# AmbaSat-08-GPS_TESEO.net
KiCad netlist of a schematic drawn in EAGLE
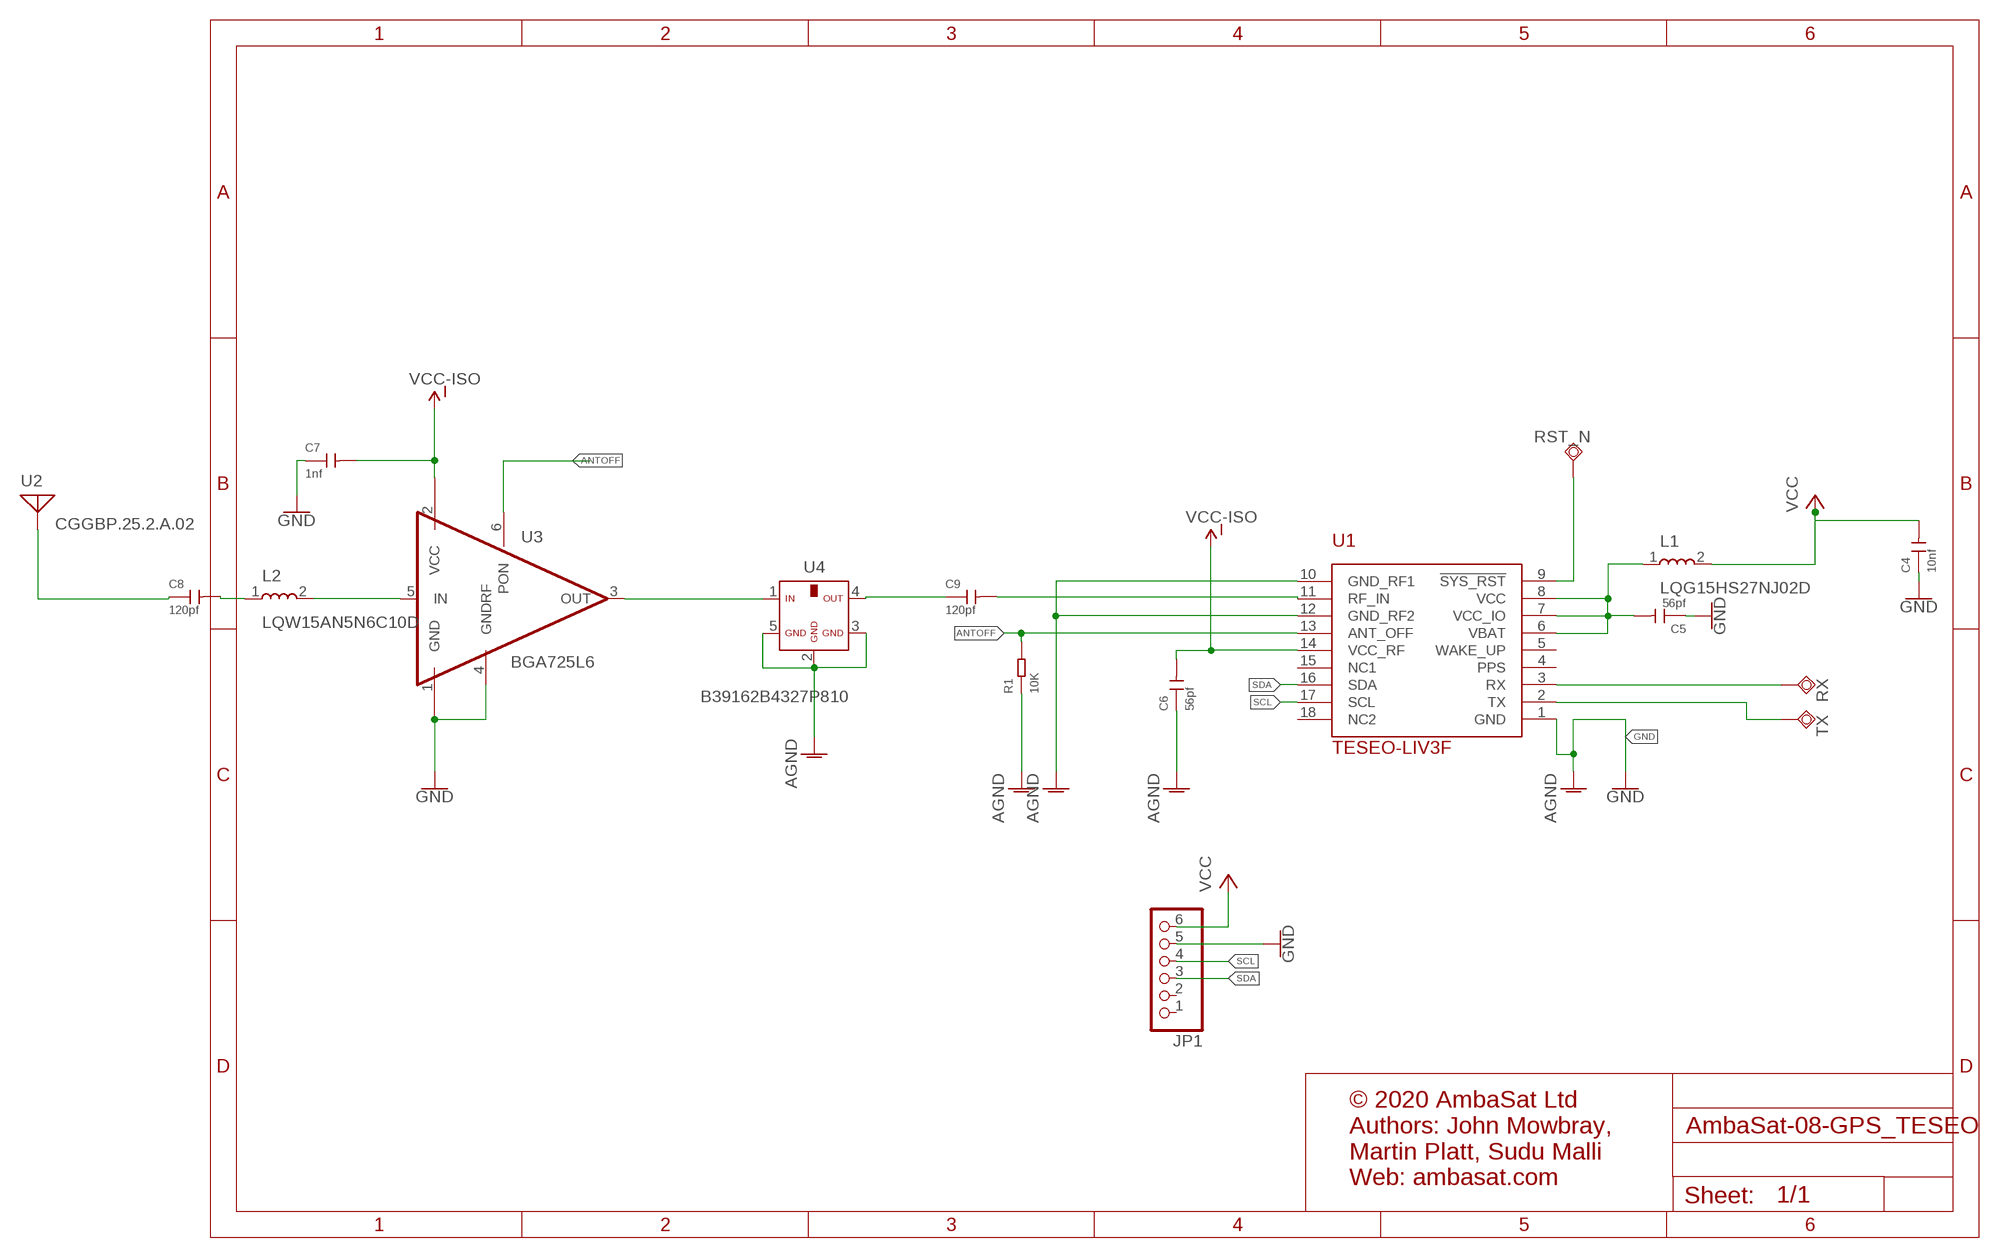
[diagram p0: schematic, sheet 1]

(export (version "E")
  (design (tool "Eeschema 10.0.6"))
  (components
    (comp (ref "C4")
      (value "10nf")
      (footprint "eagle-import:C0805")
      (fields (field (name "MPN") "CC0805JRX7R9BB103"))
      (libsource (lib "eagle-import") (part "CERAMIC-10NF-50V-5%-X7R(0805)"))
    )
    (comp (ref "C5")
      (value "56pf")
      (footprint "eagle-import:C0805")
      (fields (field (name "MPN") "CC0805JRX7R9BB103") (field (name "MPN_1") "CC0805FRNPO9BN560"))
      (libsource (lib "eagle-import") (part "CERAMIC-10NF-50V-5%-X7R(0805)"))
    )
    (comp (ref "C6")
      (value "56pf")
      (footprint "eagle-import:C0805")
      (fields (field (name "MPN") "CC0805JRX7R9BB103") (field (name "MPN_1") "CC0805FRNPO9BN560"))
      (libsource (lib "eagle-import") (part "CERAMIC-10NF-50V-5%-X7R(0805)"))
    )
    (comp (ref "C7")
      (value "1nf")
      (footprint "eagle-import:C0805")
      (fields (field (name "MPN") "CC0805JRX7R9BB103") (field (name "MPN_1") "CC0805JRX7R9BB102"))
      (libsource (lib "eagle-import") (part "CERAMIC-10NF-50V-5%-X7R(0805)"))
    )
    (comp (ref "C8")
      (value "120pf")
      (footprint "eagle-import:C0402")
      (fields (field (name "MPN") "CC0402JRNPO9BN101") (field (name "MPN_1") "CC0402JRNPO9BN121"))
      (libsource (lib "eagle-import") (part "CERAMIC-100PF-50V-5%-NPO(0402)"))
    )
    (comp (ref "C9")
      (value "120pf")
      (footprint "eagle-import:C0402")
      (fields (field (name "MPN") "CC0402JRNPO9BN101") (field (name "MPN_1") "CC0402JRNPO9BN121"))
      (libsource (lib "eagle-import") (part "CERAMIC-100PF-50V-5%-NPO(0402)"))
    )
    (comp (ref "JP1")
      (value "HEADER-1X6")
      (footprint "eagle-import:1X06_OVAL")
      (libsource (lib "eagle-import") (part "HEADER-1X6"))
    )
    (comp (ref "L1")
      (value "LQG15HS27NJ02D")
      (footprint "eagle-import:LQG15HN2N2S02D")
      (fields
        (field (name "DIGIKEY_PART_NUMBER") "490-1077-2-ND")
        (field (name "MANUFACTURER") "Murata Electronics North America")
        (field (name "MPN") "LQG15HN2N2S02D")
        (field (name "DIGIKEY_PART_NUMBER_1") "490-2628-1-ND")
        (field (name "MPN_1") "LQG15HS27NJ02D")
        (field (name "CREATED_BY") "PCBLayout.com")
      )
      (libsource (lib "eagle-import") (part "LQG15HN2N2S02D"))
    )
    (comp (ref "L2")
      (value "LQW15AN5N6C10D")
      (footprint "eagle-import:LQG15HN2N2S02D")
      (fields
        (field (name "DIGIKEY_PART_NUMBER") "490-1077-2-ND")
        (field (name "MANUFACTURER") "Murata Electronics North America")
        (field (name "MPN") "LQG15HN2N2S02D")
        (field (name "DIGIKEY_PART_NUMBER_1") "490-6833-1-ND")
        (field (name "MPN_1") "LQW15AN5N6C10D")
        (field (name "CREATED_BY") "PCBLayout.com")
      )
      (libsource (lib "eagle-import") (part "LQG15HN2N2S02D"))
    )
    (comp (ref "R1")
      (value "10K")
      (footprint "eagle-import:R0805")
      (fields (field (name "MPN") "RC0805FR-0710KL"))
      (libsource (lib "eagle-import") (part "SMD-RES-10K-1%-1/8W(0805)"))
    )
    (comp (ref "RST_N")
      (value "TESTPAD_TPSQTP11SQ")
      (footprint "eagle-import:TESTPAD_TP11SQ")
      (libsource (lib "eagle-import") (part "TESTPAD_TPSQTP11SQ"))
    )
    (comp (ref "RX")
      (value "TESTPAD_TPSQTP11SQ")
      (footprint "eagle-import:TESTPAD_TP11SQ")
      (libsource (lib "eagle-import") (part "TESTPAD_TPSQTP11SQ"))
    )
    (comp (ref "TX")
      (value "TESTPAD_TPSQTP11SQ")
      (footprint "eagle-import:TESTPAD_TP11SQ")
      (libsource (lib "eagle-import") (part "TESTPAD_TPSQTP11SQ"))
    )
    (comp (ref "U1")
      (value "TESEO-LIV3F")
      (footprint "eagle-import:TESEO-LIV3F")
      (libsource (lib "eagle-import") (part "TESEO-LIV3F"))
    )
    (comp (ref "U2")
      (value "CGGBP.25.2.A.02")
      (footprint "eagle-import:ANTENNA-PATCH")
      (libsource (lib "eagle-import") (part "CGGBP.25.2.A.02"))
    )
    (comp (ref "U3")
      (value "BGA725L6")
      (footprint "eagle-import:PSON35P100X100X35-6N")
      (fields (field (name "MPN") "BGA725L6E6327FTSA1"))
      (libsource (lib "eagle-import") (part "BGA725L6"))
    )
    (comp (ref "U4")
      (value "B39162B4327P810")
      (footprint "eagle-import:FIL_B39162B9417K610")
      (libsource (lib "eagle-import") (part "B39162B4327P810"))
    )
  )
  (nets
    (net (code "1") (name "ANTOFF") (class "Default")
      (node (ref "R1") (pin "2") (pinfunction "2_2") (pintype "passive"))
      (node (ref "U1") (pin "13") (pinfunction "ANT_OFF_13") (pintype "output"))
      (node (ref "U3") (pin "6") (pinfunction "PON_6") (pintype "power_in"))
    )
    (net (code "2") (name "GND") (class "Default")
      (node (ref "C4") (pin "1") (pinfunction "1_1") (pintype "passive"))
      (node (ref "C5") (pin "1") (pinfunction "1_1") (pintype "passive"))
      (node (ref "C6") (pin "1") (pinfunction "1_1") (pintype "passive"))
      (node (ref "C7") (pin "1") (pinfunction "1_1") (pintype "passive"))
      (node (ref "JP1") (pin "5") (pinfunction "5_5") (pintype "passive"))
      (node (ref "R1") (pin "1") (pinfunction "1_1") (pintype "passive"))
      (node (ref "U1") (pin "1") (pinfunction "GND_1") (pintype "power_in"))
      (node (ref "U1") (pin "10") (pinfunction "GND_RF1_10") (pintype "power_in"))
      (node (ref "U1") (pin "12") (pinfunction "GND_RF2_12") (pintype "power_in"))
      (node (ref "U3") (pin "1") (pinfunction "GND_1") (pintype "bidirectional"))
      (node (ref "U3") (pin "4") (pinfunction "GNDRF_4") (pintype "bidirectional"))
      (node (ref "U4") (pin "2") (pinfunction "GND3_2") (pintype "passive"))
      (node (ref "U4") (pin "3") (pinfunction "GND2_3") (pintype "passive"))
      (node (ref "U4") (pin "5") (pinfunction "GND_5") (pintype "passive"))
    )
    (net (code "3") (name "Net-(C8-Pad2)") (class "Default")
      (node (ref "C8") (pin "2") (pinfunction "2_2") (pintype "passive"))
      (node (ref "L2") (pin "1") (pinfunction "1_1") (pintype "passive"))
    )
    (net (code "4") (name "Net-(U1-RF_IN)") (class "Default")
      (node (ref "C9") (pin "2") (pinfunction "2_2") (pintype "passive"))
      (node (ref "U1") (pin "11") (pinfunction "RF_IN_11") (pintype "input"))
    )
    (net (code "5") (name "Net-(U1-RX)") (class "Default")
      (node (ref "RX") (pin "TP") (pinfunction "TP_TP") (pintype "input"))
      (node (ref "U1") (pin "3") (pinfunction "RX_3") (pintype "bidirectional"))
    )
    (net (code "6") (name "Net-(U1-TX)") (class "Default")
      (node (ref "TX") (pin "TP") (pinfunction "TP_TP") (pintype "input"))
      (node (ref "U1") (pin "2") (pinfunction "TX_2") (pintype "bidirectional"))
    )
    (net (code "7") (name "Net-(U1-VBAT)") (class "Default")
      (node (ref "C5") (pin "2") (pinfunction "2_2") (pintype "passive"))
      (node (ref "L1") (pin "1") (pinfunction "1_1") (pintype "passive"))
      (node (ref "U1") (pin "6") (pinfunction "VBAT_6") (pintype "power_in"))
      (node (ref "U1") (pin "7") (pinfunction "VCC_IO_7") (pintype "power_in"))
      (node (ref "U1") (pin "8") (pinfunction "VCC_8") (pintype "power_in"))
    )
    (net (code "8") (name "Net-(U1-~{SYS_RST})") (class "Default")
      (node (ref "RST_N") (pin "TP") (pinfunction "TP_TP") (pintype "input"))
      (node (ref "U1") (pin "9") (pinfunction "~{SYS_RST}_9") (pintype "bidirectional"))
    )
    (net (code "9") (name "Net-(U2-1)") (class "Default")
      (node (ref "C8") (pin "1") (pinfunction "1_1") (pintype "passive"))
      (node (ref "U2") (pin "ANT") (pinfunction "1_ANT") (pintype "output"))
    )
    (net (code "10") (name "Net-(U3-IN)") (class "Default")
      (node (ref "L2") (pin "2") (pinfunction "2_2") (pintype "passive"))
      (node (ref "U3") (pin "5") (pinfunction "IN_5") (pintype "input"))
    )
    (net (code "11") (name "Net-(U3-OUT)") (class "Default")
      (node (ref "U3") (pin "3") (pinfunction "OUT_3") (pintype "output"))
      (node (ref "U4") (pin "1") (pinfunction "IN_1") (pintype "passive"))
    )
    (net (code "12") (name "Net-(U4-OUT)") (class "Default")
      (node (ref "C9") (pin "1") (pinfunction "1_1") (pintype "passive"))
      (node (ref "U4") (pin "4") (pinfunction "OUT_4") (pintype "passive"))
    )
    (net (code "13") (name "SCL") (class "Default")
      (node (ref "JP1") (pin "4") (pinfunction "4_4") (pintype "passive"))
      (node (ref "U1") (pin "17") (pinfunction "SCL_17") (pintype "bidirectional"))
    )
    (net (code "14") (name "SDA") (class "Default")
      (node (ref "JP1") (pin "3") (pinfunction "3_3") (pintype "passive"))
      (node (ref "U1") (pin "16") (pinfunction "SDA_16") (pintype "bidirectional"))
    )
    (net (code "15") (name "VCC") (class "Default")
      (node (ref "C4") (pin "2") (pinfunction "2_2") (pintype "passive"))
      (node (ref "JP1") (pin "6") (pinfunction "6_6") (pintype "passive"))
      (node (ref "L1") (pin "2") (pinfunction "2_2") (pintype "passive"))
    )
    (net (code "16") (name "VCC-ISO") (class "Default")
      (node (ref "C6") (pin "2") (pinfunction "2_2") (pintype "passive"))
      (node (ref "C7") (pin "2") (pinfunction "2_2") (pintype "passive"))
      (node (ref "U1") (pin "14") (pinfunction "VCC_RF_14") (pintype "power_in"))
      (node (ref "U3") (pin "2") (pinfunction "VCC_2") (pintype "bidirectional"))
    )
    (net (code "17") (name "unconnected-(JP1-Pad1)") (class "Default")
      (node (ref "JP1") (pin "1") (pinfunction "1_1") (pintype "passive"))
    )
    (net (code "18") (name "unconnected-(JP1-Pad2)") (class "Default")
      (node (ref "JP1") (pin "2") (pinfunction "2_2") (pintype "passive"))
    )
    (net (code "19") (name "unconnected-(U1-NC1-Pad15)") (class "Default")
      (node (ref "U1") (pin "15") (pinfunction "NC1_15") (pintype "no_connect"))
    )
    (net (code "20") (name "unconnected-(U1-NC2-Pad18)") (class "Default")
      (node (ref "U1") (pin "18") (pinfunction "NC2_18") (pintype "no_connect"))
    )
    (net (code "21") (name "unconnected-(U1-PPS-Pad4)") (class "Default")
      (node (ref "U1") (pin "4") (pinfunction "PPS_4") (pintype "output"))
    )
    (net (code "22") (name "unconnected-(U1-WAKE_UP-Pad5)") (class "Default")
      (node (ref "U1") (pin "5") (pinfunction "WAKE_UP_5") (pintype "input"))
    )
  )
)
